# nico.net
KiCad netlist of a schematic drawn in EAGLE
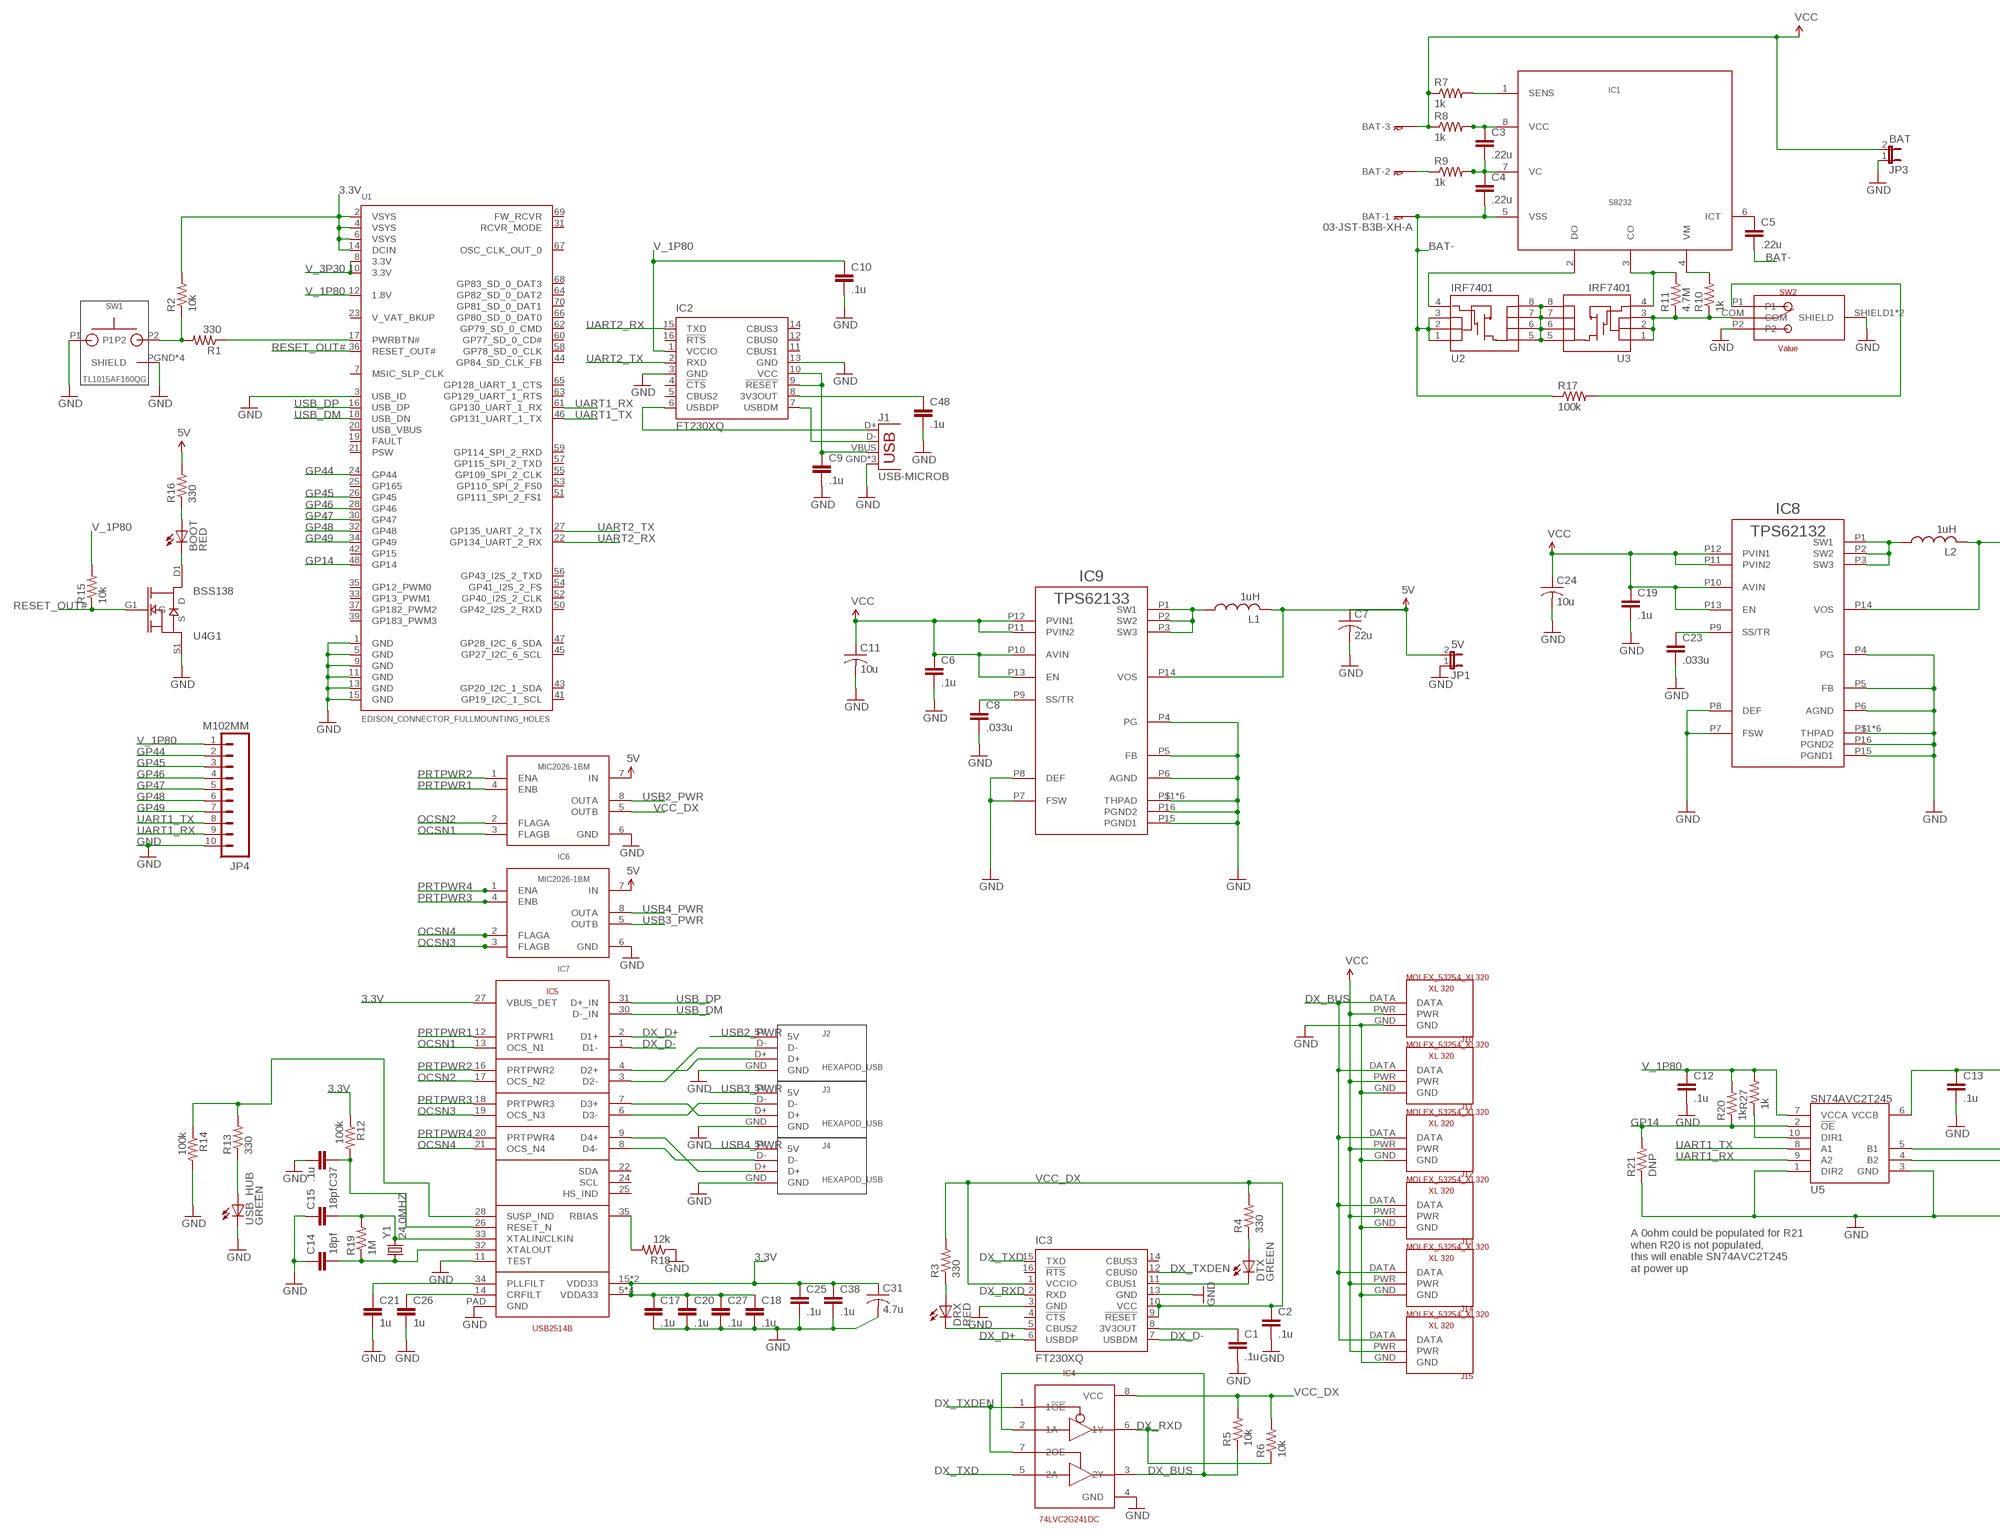
[diagram p0: schematic, sheet 1, part 1 of 2]
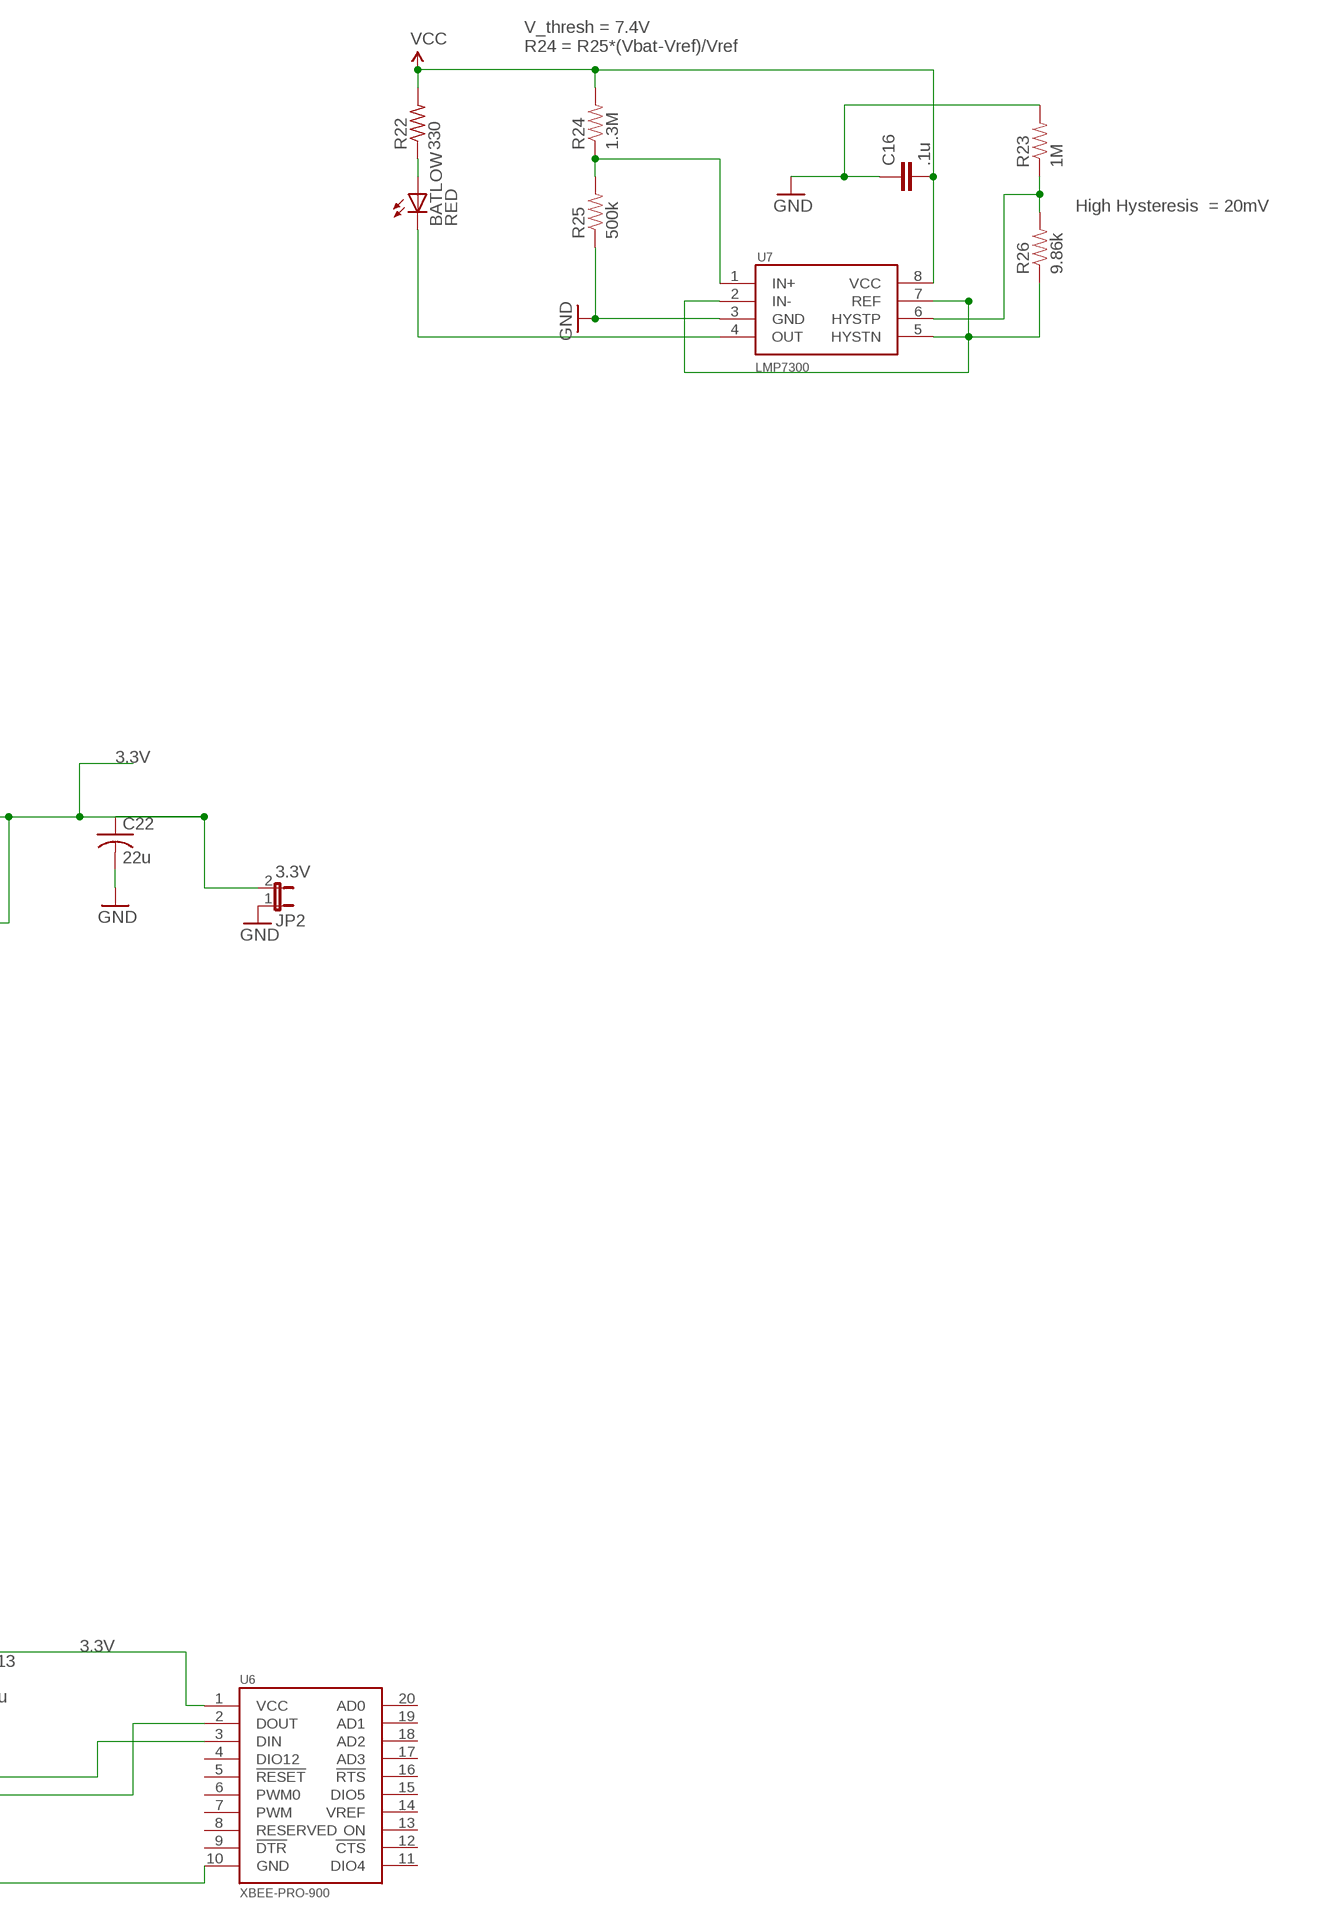
[diagram p1: schematic, sheet 1, part 2 of 2]

(export (version "E")
  (design (tool "Eeschema 10.0.6"))
  (components
    (comp (ref "BAT")
      (value "03-JST-B3B-XH-A")
      (footprint "eagle-import:B3B-XH")
      (libsource (lib "eagle-import") (part "03-JST-B3B-XH-A"))
    )
    (comp (ref "BATLOW")
      (value "RED")
      (footprint "eagle-import:LED-0603")
      (libsource (lib "eagle-import") (part "LED0603"))
    )
    (comp (ref "BOOT")
      (value "RED")
      (footprint "eagle-import:LED-0603")
      (libsource (lib "eagle-import") (part "LED0603"))
    )
    (comp (ref "C1")
      (value ".1u")
      (footprint "eagle-import:C0402")
      (libsource (lib "eagle-import") (part "C-EUC0402"))
    )
    (comp (ref "C2")
      (value ".1u")
      (footprint "eagle-import:C0402")
      (libsource (lib "eagle-import") (part "C-EUC0402"))
    )
    (comp (ref "C3")
      (value ".22u")
      (footprint "eagle-import:C0402")
      (libsource (lib "eagle-import") (part "C-EUC0402"))
    )
    (comp (ref "C4")
      (value ".22u")
      (footprint "eagle-import:C0402")
      (libsource (lib "eagle-import") (part "C-EUC0402"))
    )
    (comp (ref "C5")
      (value ".22u")
      (footprint "eagle-import:C0402")
      (libsource (lib "eagle-import") (part "C-EUC0402"))
    )
    (comp (ref "C6")
      (value ".1u")
      (footprint "eagle-import:C0402")
      (libsource (lib "eagle-import") (part "C-EUC0402"))
    )
    (comp (ref "C7")
      (value "22u")
      (footprint "eagle-import:C0603")
      (libsource (lib "eagle-import") (part "resistor_C-USC0603"))
    )
    (comp (ref "C8")
      (value ".033u")
      (footprint "eagle-import:C0402")
      (libsource (lib "eagle-import") (part "C-EUC0402"))
    )
    (comp (ref "C9")
      (value ".1u")
      (footprint "eagle-import:C0402")
      (libsource (lib "eagle-import") (part "C-EUC0402"))
    )
    (comp (ref "C10")
      (value ".1u")
      (footprint "eagle-import:C0402")
      (libsource (lib "eagle-import") (part "C-EUC0402"))
    )
    (comp (ref "C11")
      (value "10u")
      (footprint "eagle-import:C0805")
      (libsource (lib "eagle-import") (part "C-USC0805"))
    )
    (comp (ref "C12")
      (value ".1u")
      (footprint "eagle-import:C0402")
      (libsource (lib "eagle-import") (part "C-EUC0402"))
    )
    (comp (ref "C13")
      (value ".1u")
      (footprint "eagle-import:C0402")
      (libsource (lib "eagle-import") (part "C-EUC0402"))
    )
    (comp (ref "C14")
      (value "18pf")
      (footprint "eagle-import:C0402")
      (libsource (lib "eagle-import") (part "C-EUC0402"))
    )
    (comp (ref "C15")
      (value "18pf")
      (footprint "eagle-import:C0402")
      (libsource (lib "eagle-import") (part "C-EUC0402"))
    )
    (comp (ref "C16")
      (value ".1u")
      (footprint "eagle-import:C0402")
      (libsource (lib "eagle-import") (part "C-EUC0402"))
    )
    (comp (ref "C17")
      (value ".1u")
      (footprint "eagle-import:C0402")
      (libsource (lib "eagle-import") (part "C-EUC0402"))
    )
    (comp (ref "C18")
      (value ".1u")
      (footprint "eagle-import:C0402")
      (libsource (lib "eagle-import") (part "C-EUC0402"))
    )
    (comp (ref "C19")
      (value ".1u")
      (footprint "eagle-import:C0402")
      (libsource (lib "eagle-import") (part "C-EUC0402"))
    )
    (comp (ref "C20")
      (value ".1u")
      (footprint "eagle-import:C0402")
      (libsource (lib "eagle-import") (part "C-EUC0402"))
    )
    (comp (ref "C21")
      (value "1u")
      (footprint "eagle-import:C0402")
      (libsource (lib "eagle-import") (part "C-EUC0402"))
    )
    (comp (ref "C22")
      (value "22u")
      (footprint "eagle-import:C0603")
      (libsource (lib "eagle-import") (part "resistor_C-USC0603"))
    )
    (comp (ref "C23")
      (value ".033u")
      (footprint "eagle-import:C0402")
      (libsource (lib "eagle-import") (part "C-EUC0402"))
    )
    (comp (ref "C24")
      (value "10u")
      (footprint "eagle-import:C0805")
      (libsource (lib "eagle-import") (part "C-USC0805"))
    )
    (comp (ref "C25")
      (value ".1u")
      (footprint "eagle-import:C0402")
      (libsource (lib "eagle-import") (part "C-EUC0402"))
    )
    (comp (ref "C26")
      (value "1u")
      (footprint "eagle-import:C0402")
      (libsource (lib "eagle-import") (part "C-EUC0402"))
    )
    (comp (ref "C27")
      (value ".1u")
      (footprint "eagle-import:C0402")
      (libsource (lib "eagle-import") (part "C-EUC0402"))
    )
    (comp (ref "C31")
      (value "4.7u")
      (footprint "eagle-import:C0603")
      (libsource (lib "eagle-import") (part "resistor_C-USC0603"))
    )
    (comp (ref "C37")
      (value ".1u")
      (footprint "eagle-import:C0402")
      (libsource (lib "eagle-import") (part "C-EUC0402"))
    )
    (comp (ref "C38")
      (value ".1u")
      (footprint "eagle-import:C0402")
      (libsource (lib "eagle-import") (part "C-EUC0402"))
    )
    (comp (ref "C48")
      (value ".1u")
      (footprint "eagle-import:C0402")
      (libsource (lib "eagle-import") (part "C-EUC0402"))
    )
    (comp (ref "DRX")
      (value "RED")
      (footprint "eagle-import:LED-0603")
      (libsource (lib "eagle-import") (part "LED0603"))
    )
    (comp (ref "DTX")
      (value "GREEN")
      (footprint "eagle-import:LED-0603")
      (libsource (lib "eagle-import") (part "LED0603"))
    )
    (comp (ref "IC1")
      (value "S8232")
      (footprint "eagle-import:TSSOP8")
      (libsource (lib "eagle-import") (part "S8232"))
    )
    (comp (ref "IC2")
      (value "FT230XQ")
      (footprint "eagle-import:QFN16")
      (libsource (lib "eagle-import") (part "FT230XQ"))
    )
    (comp (ref "IC3")
      (value "FT230XQ")
      (footprint "eagle-import:QFN16")
      (libsource (lib "eagle-import") (part "FT230XQ"))
    )
    (comp (ref "IC4")
      (value "74LVC2G241DC")
      (footprint "eagle-import:VSSOP")
      (libsource (lib "eagle-import") (part "74LVC2G241DC"))
    )
    (comp (ref "IC5")
      (value "USB2514B")
      (footprint "eagle-import:36-QFN")
      (libsource (lib "eagle-import") (part "USB2514B"))
    )
    (comp (ref "IC6")
      (value "MIC2026-1BM")
      (footprint "eagle-import:8-SOIC")
      (libsource (lib "eagle-import") (part "MIC2026-1BM"))
    )
    (comp (ref "IC7")
      (value "MIC2026-1BM")
      (footprint "eagle-import:8-SOIC")
      (libsource (lib "eagle-import") (part "MIC2026-1BM"))
    )
    (comp (ref "IC8")
      (value "TPS62132")
      (footprint "eagle-import:VQFN-16")
      (libsource (lib "eagle-import") (part "TPS62133"))
    )
    (comp (ref "IC9")
      (value "TPS62133")
      (footprint "eagle-import:VQFN-16")
      (libsource (lib "eagle-import") (part "TPS62133"))
    )
    (comp (ref "J1")
      (value "USB-MICROB")
      (footprint "eagle-import:USB-MICROB")
      (libsource (lib "eagle-import") (part "USB-MICROB"))
    )
    (comp (ref "J2")
      (value "HEXAPOD_USB")
      (footprint "eagle-import:MOLEX_53254_4POS")
      (libsource (lib "eagle-import") (part "HEXAPOD_USB"))
    )
    (comp (ref "J3")
      (value "HEXAPOD_USB")
      (footprint "eagle-import:MOLEX_53254_4POS")
      (libsource (lib "eagle-import") (part "HEXAPOD_USB"))
    )
    (comp (ref "J4")
      (value "HEXAPOD_USB")
      (footprint "eagle-import:MOLEX_53254_4POS")
      (libsource (lib "eagle-import") (part "HEXAPOD_USB"))
    )
    (comp (ref "J10")
      (value "MOLEX_53254_XL320")
      (footprint "eagle-import:MOLES_53254_XL320")
      (libsource (lib "eagle-import") (part "MOLEX_53254_XL320"))
    )
    (comp (ref "J11")
      (value "MOLEX_53254_XL320")
      (footprint "eagle-import:MOLES_53254_XL320")
      (libsource (lib "eagle-import") (part "MOLEX_53254_XL320"))
    )
    (comp (ref "J12")
      (value "MOLEX_53254_XL320")
      (footprint "eagle-import:MOLES_53254_XL320")
      (libsource (lib "eagle-import") (part "MOLEX_53254_XL320"))
    )
    (comp (ref "J13")
      (value "MOLEX_53254_XL320")
      (footprint "eagle-import:MOLES_53254_XL320")
      (libsource (lib "eagle-import") (part "MOLEX_53254_XL320"))
    )
    (comp (ref "J14")
      (value "MOLEX_53254_XL320")
      (footprint "eagle-import:MOLES_53254_XL320")
      (libsource (lib "eagle-import") (part "MOLEX_53254_XL320"))
    )
    (comp (ref "J15")
      (value "MOLEX_53254_XL320")
      (footprint "eagle-import:MOLES_53254_XL320")
      (libsource (lib "eagle-import") (part "MOLEX_53254_XL320"))
    )
    (comp (ref "JP1")
      (value "5V")
      (footprint "eagle-import:1X02")
      (libsource (lib "eagle-import") (part "JUMPER-2PTH"))
    )
    (comp (ref "JP2")
      (value "3.3V")
      (footprint "eagle-import:1X02")
      (libsource (lib "eagle-import") (part "JUMPER-2PTH"))
    )
    (comp (ref "JP3")
      (value "BAT")
      (footprint "eagle-import:1X02")
      (libsource (lib "eagle-import") (part "JUMPER-2PTH"))
    )
    (comp (ref "JP4")
      (value "M102MM")
      (footprint "eagle-import:1X10-2MM")
      (libsource (lib "eagle-import") (part "M102MM"))
    )
    (comp (ref "L1")
      (value "1uH")
      (footprint "eagle-import:L2825P")
      (libsource (lib "eagle-import") (part "L-USL2825P"))
    )
    (comp (ref "L2")
      (value "1uH")
      (footprint "eagle-import:L2825P")
      (libsource (lib "eagle-import") (part "L-USL2825P"))
    )
    (comp (ref "R1")
      (value "330")
      (footprint "eagle-import:R0402")
      (libsource (lib "eagle-import") (part "R-US_R0402"))
    )
    (comp (ref "R2")
      (value "10k")
      (footprint "eagle-import:R0402")
      (libsource (lib "eagle-import") (part "R-US_R0402"))
    )
    (comp (ref "R3")
      (value "330")
      (footprint "eagle-import:R0402")
      (libsource (lib "eagle-import") (part "R-US_R0402"))
    )
    (comp (ref "R4")
      (value "330")
      (footprint "eagle-import:R0402")
      (libsource (lib "eagle-import") (part "R-US_R0402"))
    )
    (comp (ref "R5")
      (value "10k")
      (footprint "eagle-import:R0402")
      (libsource (lib "eagle-import") (part "R-US_R0402"))
    )
    (comp (ref "R6")
      (value "10k")
      (footprint "eagle-import:R0402")
      (libsource (lib "eagle-import") (part "R-US_R0402"))
    )
    (comp (ref "R7")
      (value "1k")
      (footprint "eagle-import:C0402")
      (libsource (lib "eagle-import") (part "RESISTOR0402"))
    )
    (comp (ref "R8")
      (value "1k")
      (footprint "eagle-import:C0402")
      (libsource (lib "eagle-import") (part "RESISTOR0402"))
    )
    (comp (ref "R9")
      (value "1k")
      (footprint "eagle-import:C0402")
      (libsource (lib "eagle-import") (part "RESISTOR0402"))
    )
    (comp (ref "R10")
      (value "1k")
      (footprint "eagle-import:C0402")
      (libsource (lib "eagle-import") (part "RESISTOR0402"))
    )
    (comp (ref "R11")
      (value "4.7M")
      (footprint "eagle-import:C0402")
      (libsource (lib "eagle-import") (part "RESISTOR0402"))
    )
    (comp (ref "R12")
      (value "100k")
      (footprint "eagle-import:C0402")
      (libsource (lib "eagle-import") (part "RESISTOR0402"))
    )
    (comp (ref "R13")
      (value "330")
      (footprint "eagle-import:R0402")
      (libsource (lib "eagle-import") (part "R-US_R0402"))
    )
    (comp (ref "R14")
      (value "100k")
      (footprint "eagle-import:C0402")
      (libsource (lib "eagle-import") (part "RESISTOR0402"))
    )
    (comp (ref "R15")
      (value "10k")
      (footprint "eagle-import:R0402")
      (libsource (lib "eagle-import") (part "R-US_R0402"))
    )
    (comp (ref "R16")
      (value "330")
      (footprint "eagle-import:R0402")
      (libsource (lib "eagle-import") (part "R-US_R0402"))
    )
    (comp (ref "R17")
      (value "100k")
      (footprint "eagle-import:C0402")
      (libsource (lib "eagle-import") (part "RESISTOR0402"))
    )
    (comp (ref "R18")
      (value "12k")
      (footprint "eagle-import:C0402")
      (libsource (lib "eagle-import") (part "RESISTOR0402"))
    )
    (comp (ref "R19")
      (value "1M")
      (footprint "eagle-import:C0402")
      (libsource (lib "eagle-import") (part "RESISTOR0402"))
    )
    (comp (ref "R20")
      (value "1k")
      (footprint "eagle-import:C0402")
      (libsource (lib "eagle-import") (part "RESISTOR0402"))
    )
    (comp (ref "R21")
      (value "DNP")
      (footprint "eagle-import:C0402")
      (libsource (lib "eagle-import") (part "RESISTOR0402"))
    )
    (comp (ref "R22")
      (value "330")
      (footprint "eagle-import:R0402")
      (libsource (lib "eagle-import") (part "R-US_R0402"))
    )
    (comp (ref "R23")
      (value "1M")
      (footprint "eagle-import:C0402")
      (libsource (lib "eagle-import") (part "RESISTOR0402"))
    )
    (comp (ref "R24")
      (value "1.3M")
      (footprint "eagle-import:C0402")
      (libsource (lib "eagle-import") (part "RESISTOR0402"))
    )
    (comp (ref "R25")
      (value "500k")
      (footprint "eagle-import:C0402")
      (libsource (lib "eagle-import") (part "RESISTOR0402"))
    )
    (comp (ref "R26")
      (value "9.86k")
      (footprint "eagle-import:C0402")
      (libsource (lib "eagle-import") (part "RESISTOR0402"))
    )
    (comp (ref "R27")
      (value "1k")
      (footprint "eagle-import:C0402")
      (libsource (lib "eagle-import") (part "RESISTOR0402"))
    )
    (comp (ref "SW1")
      (value "TL1015AF160QG")
      (footprint "eagle-import:TL1015AF160QG")
      (libsource (lib "eagle-import") (part "TL1015AF160QG"))
    )
    (comp (ref "SW2")
      (value "TOGGLE_SWITCH_ET01MD1AGE")
      (footprint "eagle-import:TOGGLE_SWITCH_ET01MD1AGE")
      (libsource (lib "eagle-import") (part "TOGGLE_SWITCH_ET01MD1AGE"))
    )
    (comp (ref "U1")
      (value "EDISON_CONNECTOR_FULLMOUNTING_HOLES")
      (footprint "eagle-import:EDISON_DAUGHTER")
      (libsource (lib "eagle-import") (part "EDISON_CONNECTOR_FULLMOUNTING_HOLES"))
    )
    (comp (ref "U2")
      (value "IRF7401")
      (footprint "eagle-import:SO08")
      (libsource (lib "eagle-import") (part "MOSFET-NCHANNEL-SOIC8"))
    )
    (comp (ref "U3")
      (value "IRF7401")
      (footprint "eagle-import:SO08")
      (libsource (lib "eagle-import") (part "MOSFET-NCHANNEL-SOIC8"))
    )
    (comp (ref "U4")
      (value "BSS138")
      (footprint "eagle-import:SOT363")
      (libsource (lib "eagle-import") (part "BSS138"))
    )
    (comp (ref "U5")
      (value "SN74AVC2T245")
      (footprint "eagle-import:RSW-UQFN-10")
      (libsource (lib "eagle-import") (part "SN74AVC2T245"))
    )
    (comp (ref "U6")
      (value "XBEE-PRO-900")
      (footprint "eagle-import:XBEE-PRO-OEM")
      (libsource (lib "eagle-import") (part "XBEE-PRO-900"))
    )
    (comp (ref "U7")
      (value "LMP7300")
      (footprint "eagle-import:8-SOIC")
      (libsource (lib "eagle-import") (part "LMP7300"))
    )
    (comp (ref "USB_HUB")
      (value "GREEN")
      (footprint "eagle-import:LED-0603")
      (libsource (lib "eagle-import") (part "LED0603"))
    )
    (comp (ref "Y1")
      (value "24.0MHZ")
      (footprint "eagle-import:CRYSTAL-SMD-5X3")
      (libsource (lib "eagle-import") (part "CRYSTAL5X3"))
    )
  )
  (nets
    (net (code "1") (name "/3.3V") (class "Default")
      (node (ref "C13") (pin "1") (pinfunction "1_1") (pintype "passive"))
      (node (ref "C17") (pin "1") (pinfunction "1_1") (pintype "passive"))
      (node (ref "C18") (pin "1") (pinfunction "1_1") (pintype "passive"))
      (node (ref "C20") (pin "1") (pinfunction "1_1") (pintype "passive"))
      (node (ref "C22") (pin "1") (pinfunction "1_1") (pintype "passive"))
      (node (ref "C25") (pin "1") (pinfunction "1_1") (pintype "passive"))
      (node (ref "C27") (pin "1") (pinfunction "1_1") (pintype "passive"))
      (node (ref "C31") (pin "1") (pinfunction "1_1") (pintype "passive"))
      (node (ref "C38") (pin "1") (pinfunction "1_1") (pintype "passive"))
      (node (ref "IC5") (pin "10") (pinfunction "VDDA33_10") (pintype "bidirectional"))
      (node (ref "IC5") (pin "15") (pinfunction "VDD33_15") (pintype "bidirectional"))
      (node (ref "IC5") (pin "23") (pinfunction "VDD33_23") (pintype "bidirectional"))
      (node (ref "IC5") (pin "27") (pinfunction "VBUS_DET_27") (pintype "bidirectional"))
      (node (ref "IC5") (pin "29") (pinfunction "VDDA33_29") (pintype "bidirectional"))
      (node (ref "IC5") (pin "36") (pinfunction "VDDA33_36") (pintype "bidirectional"))
      (node (ref "IC5") (pin "5") (pinfunction "VDDA33_5") (pintype "bidirectional"))
      (node (ref "IC8") (pin "P14") (pinfunction "VOS_P14") (pintype "bidirectional"))
      (node (ref "JP2") (pin "2") (pinfunction "2_2") (pintype "passive"))
      (node (ref "L2") (pin "2") (pinfunction "2_2") (pintype "passive"))
      (node (ref "R12") (pin "1") (pinfunction "1_1") (pintype "passive"))
      (node (ref "R2") (pin "2") (pinfunction "2_2") (pintype "passive"))
      (node (ref "U1") (pin "14") (pinfunction "DCIN_14") (pintype "bidirectional"))
      (node (ref "U1") (pin "2") (pinfunction "VSYS_2") (pintype "bidirectional"))
      (node (ref "U1") (pin "4") (pinfunction "VSYS_4") (pintype "bidirectional"))
      (node (ref "U1") (pin "6") (pinfunction "VSYS_6") (pintype "bidirectional"))
      (node (ref "U5") (pin "6") (pinfunction "VCCB_6") (pintype "bidirectional"))
      (node (ref "U6") (pin "1") (pinfunction "VCC_1") (pintype "bidirectional"))
    )
    (net (code "2") (name "/BAT-") (class "Default")
      (node (ref "BAT") (pin "P$1") (pinfunction "1_P$1") (pintype "passive"))
      (node (ref "C4") (pin "2") (pinfunction "2_2") (pintype "passive"))
      (node (ref "C5") (pin "2") (pinfunction "2_2") (pintype "passive"))
      (node (ref "IC1") (pin "5") (pinfunction "VSS_5") (pintype "bidirectional"))
      (node (ref "R17") (pin "1") (pinfunction "1_1") (pintype "passive"))
      (node (ref "U2") (pin "1") (pinfunction "S_1") (pintype "bidirectional"))
      (node (ref "U2") (pin "2") (pinfunction "S_2") (pintype "bidirectional"))
      (node (ref "U2") (pin "3") (pinfunction "S_3") (pintype "bidirectional"))
    )
    (net (code "3") (name "/DX_BUS") (class "Default")
      (node (ref "IC4") (pin "2") (pinfunction "1A_2") (pintype "bidirectional"))
      (node (ref "IC4") (pin "3") (pinfunction "2Y_3") (pintype "bidirectional"))
      (node (ref "J10") (pin "DATA") (pinfunction "DATA_DATA") (pintype "bidirectional"))
      (node (ref "J11") (pin "DATA") (pinfunction "DATA_DATA") (pintype "bidirectional"))
      (node (ref "J12") (pin "DATA") (pinfunction "DATA_DATA") (pintype "bidirectional"))
      (node (ref "J13") (pin "DATA") (pinfunction "DATA_DATA") (pintype "bidirectional"))
      (node (ref "J14") (pin "DATA") (pinfunction "DATA_DATA") (pintype "bidirectional"))
      (node (ref "J15") (pin "DATA") (pinfunction "DATA_DATA") (pintype "bidirectional"))
      (node (ref "R5") (pin "1") (pinfunction "1_1") (pintype "passive"))
    )
    (net (code "4") (name "/DX_D+") (class "Default")
      (node (ref "IC3") (pin "6") (pinfunction "USBDP_6") (pintype "input"))
      (node (ref "IC5") (pin "2") (pinfunction "D1+_2") (pintype "bidirectional"))
    )
    (net (code "5") (name "/DX_D-") (class "Default")
      (node (ref "IC3") (pin "7") (pinfunction "USBDM_7") (pintype "input"))
      (node (ref "IC5") (pin "1") (pinfunction "D1-_1") (pintype "bidirectional"))
    )
    (net (code "6") (name "/DX_RXD") (class "Default")
      (node (ref "IC3") (pin "2") (pinfunction "RXD_2") (pintype "input"))
      (node (ref "IC4") (pin "6") (pinfunction "1Y_6") (pintype "bidirectional"))
      (node (ref "R6") (pin "1") (pinfunction "1_1") (pintype "passive"))
    )
    (net (code "7") (name "/DX_TXD") (class "Default")
      (node (ref "IC3") (pin "15") (pinfunction "TXD_15") (pintype "output"))
      (node (ref "IC4") (pin "5") (pinfunction "2A_5") (pintype "bidirectional"))
    )
    (net (code "8") (name "/DX_TXDEN") (class "Default")
      (node (ref "IC3") (pin "12") (pinfunction "CBUS0_12") (pintype "bidirectional"))
      (node (ref "IC4") (pin "1") (pinfunction "1~{OE}_1") (pintype "bidirectional"))
      (node (ref "IC4") (pin "7") (pinfunction "2OE_7") (pintype "bidirectional"))
    )
    (net (code "9") (name "/GP14") (class "Default")
      (node (ref "R20") (pin "1") (pinfunction "1_1") (pintype "passive"))
      (node (ref "R21") (pin "2") (pinfunction "2_2") (pintype "passive"))
      (node (ref "U1") (pin "48") (pinfunction "GP14_48") (pintype "bidirectional"))
      (node (ref "U5") (pin "2") (pinfunction "~{OE}_2") (pintype "bidirectional"))
    )
    (net (code "10") (name "/GP44") (class "Default")
      (node (ref "JP4") (pin "2") (pinfunction "2_2") (pintype "passive"))
      (node (ref "U1") (pin "24") (pinfunction "GP44_24") (pintype "bidirectional"))
    )
    (net (code "11") (name "/GP45") (class "Default")
      (node (ref "JP4") (pin "3") (pinfunction "3_3") (pintype "passive"))
      (node (ref "U1") (pin "26") (pinfunction "GP45_26") (pintype "bidirectional"))
    )
    (net (code "12") (name "/GP46") (class "Default")
      (node (ref "JP4") (pin "4") (pinfunction "4_4") (pintype "passive"))
      (node (ref "U1") (pin "28") (pinfunction "GP46_28") (pintype "bidirectional"))
    )
    (net (code "13") (name "/GP47") (class "Default")
      (node (ref "JP4") (pin "5") (pinfunction "5_5") (pintype "passive"))
      (node (ref "U1") (pin "30") (pinfunction "GP47_30") (pintype "bidirectional"))
    )
    (net (code "14") (name "/GP48") (class "Default")
      (node (ref "JP4") (pin "6") (pinfunction "6_6") (pintype "passive"))
      (node (ref "U1") (pin "32") (pinfunction "GP48_32") (pintype "bidirectional"))
    )
    (net (code "15") (name "/GP49") (class "Default")
      (node (ref "JP4") (pin "7") (pinfunction "7_7") (pintype "passive"))
      (node (ref "U1") (pin "34") (pinfunction "GP49_34") (pintype "bidirectional"))
    )
    (net (code "16") (name "/OCSN1") (class "Default")
      (node (ref "IC5") (pin "13") (pinfunction "OCS_N1_13") (pintype "bidirectional"))
      (node (ref "IC6") (pin "3") (pinfunction "FLAGB_3") (pintype "bidirectional"))
    )
    (net (code "17") (name "/OCSN2") (class "Default")
      (node (ref "IC5") (pin "17") (pinfunction "OCS_N2_17") (pintype "bidirectional"))
      (node (ref "IC6") (pin "2") (pinfunction "FLAGA_2") (pintype "bidirectional"))
    )
    (net (code "18") (name "/OCSN3") (class "Default")
      (node (ref "IC5") (pin "19") (pinfunction "OCS_N3_19") (pintype "bidirectional"))
      (node (ref "IC7") (pin "3") (pinfunction "FLAGB_3") (pintype "bidirectional"))
    )
    (net (code "19") (name "/OCSN4") (class "Default")
      (node (ref "IC5") (pin "21") (pinfunction "OCS_N4_21") (pintype "bidirectional"))
      (node (ref "IC7") (pin "2") (pinfunction "FLAGA_2") (pintype "bidirectional"))
    )
    (net (code "20") (name "/PRTPWR1") (class "Default")
      (node (ref "IC5") (pin "12") (pinfunction "PRTPWR1_12") (pintype "bidirectional"))
      (node (ref "IC6") (pin "4") (pinfunction "ENB_4") (pintype "bidirectional"))
    )
    (net (code "21") (name "/PRTPWR2") (class "Default")
      (node (ref "IC5") (pin "16") (pinfunction "PRTPWR2_16") (pintype "bidirectional"))
      (node (ref "IC6") (pin "1") (pinfunction "ENA_1") (pintype "bidirectional"))
    )
    (net (code "22") (name "/PRTPWR3") (class "Default")
      (node (ref "IC5") (pin "18") (pinfunction "PRTPWR3_18") (pintype "bidirectional"))
      (node (ref "IC7") (pin "4") (pinfunction "ENB_4") (pintype "bidirectional"))
    )
    (net (code "23") (name "/PRTPWR4") (class "Default")
      (node (ref "IC5") (pin "20") (pinfunction "PRTPWR4_20") (pintype "bidirectional"))
      (node (ref "IC7") (pin "1") (pinfunction "ENA_1") (pintype "bidirectional"))
    )
    (net (code "24") (name "/RESET_OUT#") (class "Default")
      (node (ref "R15") (pin "1") (pinfunction "1_1") (pintype "passive"))
      (node (ref "U1") (pin "36") (pinfunction "RESET_OUT#_36") (pintype "bidirectional"))
      (node (ref "U4") (pin "G1") (pinfunction "G_G1") (pintype "bidirectional"))
    )
    (net (code "25") (name "/UART1_RX") (class "Default")
      (node (ref "JP4") (pin "9") (pinfunction "9_9") (pintype "passive"))
      (node (ref "U1") (pin "61") (pinfunction "GP130_UART_1_RX_61") (pintype "bidirectional"))
      (node (ref "U5") (pin "9") (pinfunction "A2_9") (pintype "bidirectional"))
    )
    (net (code "26") (name "/UART1_TX") (class "Default")
      (node (ref "JP4") (pin "8") (pinfunction "8_8") (pintype "passive"))
      (node (ref "U1") (pin "46") (pinfunction "GP131_UART_1_TX_46") (pintype "bidirectional"))
      (node (ref "U5") (pin "8") (pinfunction "A1_8") (pintype "bidirectional"))
    )
    (net (code "27") (name "/UART2_RX") (class "Default")
      (node (ref "IC2") (pin "15") (pinfunction "TXD_15") (pintype "output"))
      (node (ref "U1") (pin "22") (pinfunction "GP134_UART_2_RX_22") (pintype "bidirectional"))
    )
    (net (code "28") (name "/UART2_TX") (class "Default")
      (node (ref "IC2") (pin "2") (pinfunction "RXD_2") (pintype "input"))
      (node (ref "U1") (pin "27") (pinfunction "GP135_UART_2_TX_27") (pintype "bidirectional"))
    )
    (net (code "29") (name "/USB2_PWR") (class "Default")
      (node (ref "IC6") (pin "8") (pinfunction "OUTA_8") (pintype "bidirectional"))
      (node (ref "J2") (pin "5V") (pinfunction "5V_5V") (pintype "bidirectional"))
    )
    (net (code "30") (name "/USB3_PWR") (class "Default")
      (node (ref "IC7") (pin "5") (pinfunction "OUTB_5") (pintype "bidirectional"))
      (node (ref "J3") (pin "5V") (pinfunction "5V_5V") (pintype "bidirectional"))
    )
    (net (code "31") (name "/USB4_PWR") (class "Default")
      (node (ref "IC7") (pin "8") (pinfunction "OUTA_8") (pintype "bidirectional"))
      (node (ref "J4") (pin "5V") (pinfunction "5V_5V") (pintype "bidirectional"))
    )
    (net (code "32") (name "/USB_DM") (class "Default")
      (node (ref "IC5") (pin "30") (pinfunction "D-_IN_30") (pintype "bidirectional"))
      (node (ref "U1") (pin "18") (pinfunction "USB_DN_18") (pintype "bidirectional"))
    )
    (net (code "33") (name "/USB_DP") (class "Default")
      (node (ref "IC5") (pin "31") (pinfunction "D+_IN_31") (pintype "bidirectional"))
      (node (ref "U1") (pin "16") (pinfunction "USB_DP_16") (pintype "bidirectional"))
    )
    (net (code "34") (name "/VCC_DX") (class "Default")
      (node (ref "C2") (pin "1") (pinfunction "1_1") (pintype "passive"))
      (node (ref "IC3") (pin "1") (pinfunction "VCCIO_1") (pintype "power_in"))
      (node (ref "IC3") (pin "10") (pinfunction "VCC_10") (pintype "power_in"))
      (node (ref "IC3") (pin "9") (pinfunction "~{RESET}_9") (pintype "input"))
      (node (ref "IC4") (pin "8") (pinfunction "VCC_8") (pintype "bidirectional"))
      (node (ref "IC6") (pin "5") (pinfunction "OUTB_5") (pintype "bidirectional"))
      (node (ref "R3") (pin "2") (pinfunction "2_2") (pintype "passive"))
      (node (ref "R4") (pin "2") (pinfunction "2_2") (pintype "passive"))
      (node (ref "R5") (pin "2") (pinfunction "2_2") (pintype "passive"))
      (node (ref "R6") (pin "2") (pinfunction "2_2") (pintype "passive"))
    )
    (net (code "35") (name "/V_1P80") (class "Default")
      (node (ref "C10") (pin "1") (pinfunction "1_1") (pintype "passive"))
      (node (ref "C12") (pin "1") (pinfunction "1_1") (pintype "passive"))
      (node (ref "IC2") (pin "1") (pinfunction "VCCIO_1") (pintype "power_in"))
      (node (ref "JP4") (pin "1") (pinfunction "1_1") (pintype "passive"))
      (node (ref "R15") (pin "2") (pinfunction "2_2") (pintype "passive"))
      (node (ref "R20") (pin "2") (pinfunction "2_2") (pintype "passive"))
      (node (ref "R27") (pin "2") (pinfunction "2_2") (pintype "passive"))
      (node (ref "U1") (pin "12") (pinfunction "1.8V_12") (pintype "bidirectional"))
      (node (ref "U5") (pin "7") (pinfunction "VCCA_7") (pintype "bidirectional"))
    )
    (net (code "36") (name "/V_3P30") (class "Default")
      (node (ref "U1") (pin "10") (pinfunction "3.3V_10") (pintype "bidirectional"))
      (node (ref "U1") (pin "8") (pinfunction "3.3V_8") (pintype "bidirectional"))
    )
    (net (code "37") (name "5V") (class "Default")
      (node (ref "C7") (pin "1") (pinfunction "1_1") (pintype "passive"))
      (node (ref "IC6") (pin "7") (pinfunction "IN_7") (pintype "bidirectional"))
      (node (ref "IC7") (pin "7") (pinfunction "IN_7") (pintype "bidirectional"))
      (node (ref "IC9") (pin "P14") (pinfunction "VOS_P14") (pintype "bidirectional"))
      (node (ref "JP1") (pin "2") (pinfunction "2_2") (pintype "passive"))
      (node (ref "L1") (pin "2") (pinfunction "2_2") (pintype "passive"))
      (node (ref "R16") (pin "2") (pinfunction "2_2") (pintype "passive"))
    )
    (net (code "38") (name "GND") (class "Default")
      (node (ref "C1") (pin "2") (pinfunction "2_2") (pintype "passive"))
      (node (ref "C10") (pin "2") (pinfunction "2_2") (pintype "passive"))
      (node (ref "C11") (pin "2") (pinfunction "2_2") (pintype "passive"))
      (node (ref "C12") (pin "2") (pinfunction "2_2") (pintype "passive"))
      (node (ref "C13") (pin "2") (pinfunction "2_2") (pintype "passive"))
      (node (ref "C14") (pin "1") (pinfunction "1_1") (pintype "passive"))
      (node (ref "C15") (pin "1") (pinfunction "1_1") (pintype "passive"))
      (node (ref "C16") (pin "1") (pinfunction "1_1") (pintype "passive"))
      (node (ref "C17") (pin "2") (pinfunction "2_2") (pintype "passive"))
      (node (ref "C18") (pin "2") (pinfunction "2_2") (pintype "passive"))
      (node (ref "C19") (pin "2") (pinfunction "2_2") (pintype "passive"))
      (node (ref "C2") (pin "2") (pinfunction "2_2") (pintype "passive"))
      (node (ref "C20") (pin "2") (pinfunction "2_2") (pintype "passive"))
      (node (ref "C21") (pin "2") (pinfunction "2_2") (pintype "passive"))
      (node (ref "C22") (pin "2") (pinfunction "2_2") (pintype "passive"))
      (node (ref "C23") (pin "2") (pinfunction "2_2") (pintype "passive"))
      (node (ref "C24") (pin "2") (pinfunction "2_2") (pintype "passive"))
      (node (ref "C25") (pin "2") (pinfunction "2_2") (pintype "passive"))
      (node (ref "C26") (pin "2") (pinfunction "2_2") (pintype "passive"))
      (node (ref "C27") (pin "2") (pinfunction "2_2") (pintype "passive"))
      (node (ref "C31") (pin "2") (pinfunction "2_2") (pintype "passive"))
      (node (ref "C37") (pin "2") (pinfunction "2_2") (pintype "passive"))
      (node (ref "C38") (pin "2") (pinfunction "2_2") (pintype "passive"))
      (node (ref "C48") (pin "2") (pinfunction "2_2") (pintype "passive"))
      (node (ref "C6") (pin "2") (pinfunction "2_2") (pintype "passive"))
      (node (ref "C7") (pin "2") (pinfunction "2_2") (pintype "passive"))
      (node (ref "C8") (pin "2") (pinfunction "2_2") (pintype "passive"))
      (node (ref "C9") (pin "2") (pinfunction "2_2") (pintype "passive"))
      (node (ref "IC2") (pin "13") (pinfunction "GND_13") (pintype "power_in"))
      (node (ref "IC2") (pin "3") (pinfunction "GND_3") (pintype "power_in"))
      (node (ref "IC3") (pin "13") (pinfunction "GND_13") (pintype "power_in"))
      (node (ref "IC3") (pin "3") (pinfunction "GND_3") (pintype "power_in"))
      (node (ref "IC4") (pin "4") (pinfunction "GND_4") (pintype "bidirectional"))
      (node (ref "IC5") (pin "11") (pinfunction "TEST_11") (pintype "bidirectional"))
      (node (ref "IC5") (pin "PAD") (pinfunction "GND_PAD") (pintype "bidirectional"))
      (node (ref "IC6") (pin "6") (pinfunction "GND_6") (pintype "bidirectional"))
      (node (ref "IC7") (pin "6") (pinfunction "GND_6") (pintype "bidirectional"))
      (node (ref "IC8") (pin "P$1") (pinfunction "THPAD_P$1") (pintype "bidirectional"))
      (node (ref "IC8") (pin "P$2") (pinfunction "THPAD_P$2") (pintype "bidirectional"))
      (node (ref "IC8") (pin "P$3") (pinfunction "THPAD_P$3") (pintype "bidirectional"))
      (node (ref "IC8") (pin "P$4") (pinfunction "THPAD_P$4") (pintype "bidirectional"))
      (node (ref "IC8") (pin "P$5") (pinfunction "THPAD_P$5") (pintype "bidirectional"))
      (node (ref "IC8") (pin "P$6") (pinfunction "THPAD_P$6") (pintype "bidirectional"))
      (node (ref "IC8") (pin "P15") (pinfunction "PGND1_P15") (pintype "bidirectional"))
      (node (ref "IC8") (pin "P16") (pinfunction "PGND2_P16") (pintype "bidirectional"))
      (node (ref "IC8") (pin "P4") (pinfunction "PG_P4") (pintype "bidirectional"))
      (node (ref "IC8") (pin "P5") (pinfunction "FB_P5") (pintype "bidirectional"))
      (node (ref "IC8") (pin "P6") (pinfunction "AGND_P6") (pintype "bidirectional"))
      (node (ref "IC8") (pin "P7") (pinfunction "FSW_P7") (pintype "bidirectional"))
      (node (ref "IC8") (pin "P8") (pinfunction "DEF_P8") (pintype "bidirectional"))
      (node (ref "IC9") (pin "P$1") (pinfunction "THPAD_P$1") (pintype "bidirectional"))
      (node (ref "IC9") (pin "P$2") (pinfunction "THPAD_P$2") (pintype "bidirectional"))
      (node (ref "IC9") (pin "P$3") (pinfunction "THPAD_P$3") (pintype "bidirectional"))
      (node (ref "IC9") (pin "P$4") (pinfunction "THPAD_P$4") (pintype "bidirectional"))
      (node (ref "IC9") (pin "P$5") (pinfunction "THPAD_P$5") (pintype "bidirectional"))
      (node (ref "IC9") (pin "P$6") (pinfunction "THPAD_P$6") (pintype "bidirectional"))
      (node (ref "IC9") (pin "P15") (pinfunction "PGND1_P15") (pintype "bidirectional"))
      (node (ref "IC9") (pin "P16") (pinfunction "PGND2_P16") (pintype "bidirectional"))
      (node (ref "IC9") (pin "P4") (pinfunction "PG_P4") (pintype "bidirectional"))
      (node (ref "IC9") (pin "P5") (pinfunction "FB_P5") (pintype "bidirectional"))
      (node (ref "IC9") (pin "P6") (pinfunction "AGND_P6") (pintype "bidirectional"))
      (node (ref "IC9") (pin "P7") (pinfunction "FSW_P7") (pintype "bidirectional"))
      (node (ref "IC9") (pin "P8") (pinfunction "DEF_P8") (pintype "bidirectional"))
      (node (ref "J1") (pin "GND") (pinfunction "GND_GND") (pintype "bidirectional"))
      (node (ref "J1") (pin "MT1") (pinfunction "GND_MT1") (pintype "bidirectional"))
      (node (ref "J1") (pin "MT2") (pinfunction "GND_MT2") (pintype "bidirectional"))
      (node (ref "J10") (pin "GND") (pinfunction "GND_GND") (pintype "bidirectional"))
      (node (ref "J11") (pin "GND") (pinfunction "GND_GND") (pintype "bidirectional"))
      (node (ref "J12") (pin "GND") (pinfunction "GND_GND") (pintype "bidirectional"))
      (node (ref "J13") (pin "GND") (pinfunction "GND_GND") (pintype "bidirectional"))
      (node (ref "J14") (pin "GND") (pinfunction "GND_GND") (pintype "bidirectional"))
      (node (ref "J15") (pin "GND") (pinfunction "GND_GND") (pintype "bidirectional"))
      (node (ref "J2") (pin "GND") (pinfunction "GND_GND") (pintype "bidirectional"))
      (node (ref "J3") (pin "GND") (pinfunction "GND_GND") (pintype "bidirectional"))
      (node (ref "J4") (pin "GND") (pinfunction "GND_GND") (pintype "bidirectional"))
      (node (ref "JP1") (pin "1") (pinfunction "1_1") (pintype "passive"))
      (node (ref "JP2") (pin "1") (pinfunction "1_1") (pintype "passive"))
      (node (ref "JP3") (pin "1") (pinfunction "1_1") (pintype "passive"))
      (node (ref "JP4") (pin "10") (pinfunction "10_10") (pintype "passive"))
      (node (ref "R14") (pin "2") (pinfunction "2_2") (pintype "passive"))
      (node (ref "R18") (pin "1") (pinfunction "1_1") (pintype "passive"))
      (node (ref "R21") (pin "1") (pinfunction "1_1") (pintype "passive"))
      (node (ref "R23") (pin "2") (pinfunction "2_2") (pintype "passive"))
      (node (ref "R25") (pin "1") (pinfunction "1_1") (pintype "passive"))
      (node (ref "SW1") (pin "P1") (pinfunction "P1_P1") (pintype "bidirectional"))
      (node (ref "SW1") (pin "PGND") (pinfunction "SHIELD_PGND") (pintype "bidirectional"))
      (node (ref "SW1") (pin "PGND2") (pinfunction "SHIELD_PGND2") (pintype "bidirectional"))
      (node (ref "SW1") (pin "PGND3") (pinfunction "SHIELD_PGND3") (pintype "bidirectional"))
      (node (ref "SW1") (pin "PGND4") (pinfunction "SHIELD_PGND4") (pintype "bidirectional"))
      (node (ref "SW2") (pin "P2") (pinfunction "P2_P2") (pintype "bidirectional"))
      (node (ref "SW2") (pin "SHIELD1") (pinfunction "SHIELD_SHIELD1") (pintype "bidirectional"))
      (node (ref "SW2") (pin "SHIELD2") (pinfunction "SHIELD_SHIELD2") (pintype "bidirectional"))
      (node (ref "U1") (pin "1") (pinfunction "GND_1") (pintype "bidirectional"))
      (node (ref "U1") (pin "11") (pinfunction "GND_11") (pintype "bidirectional"))
      (node (ref "U1") (pin "13") (pinfunction "GND_13") (pintype "bidirectional"))
      (node (ref "U1") (pin "15") (pinfunction "GND_15") (pintype "bidirectional"))
      (node (ref "U1") (pin "3") (pinfunction "USB_ID_3") (pintype "bidirectional"))
      (node (ref "U1") (pin "5") (pinfunction "GND_5") (pintype "bidirectional"))
      (node (ref "U1") (pin "9") (pinfunction "GND_9") (pintype "bidirectional"))
      (node (ref "U4") (pin "S1") (pinfunction "S_S1") (pintype "bidirectional"))
      (node (ref "U5") (pin "1") (pinfunction "DIR2_1") (pintype "bidirectional"))
      (node (ref "U5") (pin "3") (pinfunction "GND_3") (pintype "bidirectional"))
      (node (ref "U6") (pin "10") (pinfunction "GND_10") (pintype "bidirectional"))
      (node (ref "U7") (pin "3") (pinfunction "GND_3") (pintype "bidirectional"))
      (node (ref "USB_HUB") (pin "C") (pinfunction "C_C") (pintype "passive"))
    )
    (net (code "39") (name "Net-(BATB-1)") (class "Default")
      (node (ref "BAT") (pin "P$2") (pinfunction "1_P$2") (pintype "passive"))
      (node (ref "R9") (pin "1") (pinfunction "1_1") (pintype "passive"))
    )
    (net (code "40") (name "Net-(BATLOW-PadA)") (class "Default")
      (node (ref "BATLOW") (pin "A") (pinfunction "A_A") (pintype "passive"))
      (node (ref "R22") (pin "1") (pinfunction "1_1") (pintype "passive"))
    )
    (net (code "41") (name "Net-(BOOT-PadA)") (class "Default")
      (node (ref "BOOT") (pin "A") (pinfunction "A_A") (pintype "passive"))
      (node (ref "R16") (pin "1") (pinfunction "1_1") (pintype "passive"))
    )
    (net (code "42") (name "Net-(DRX-PadA)") (class "Default")
      (node (ref "DRX") (pin "A") (pinfunction "A_A") (pintype "passive"))
      (node (ref "R3") (pin "1") (pinfunction "1_1") (pintype "passive"))
    )
    (net (code "43") (name "Net-(DTX-PadA)") (class "Default")
      (node (ref "DTX") (pin "A") (pinfunction "A_A") (pintype "passive"))
      (node (ref "R4") (pin "1") (pinfunction "1_1") (pintype "passive"))
    )
    (net (code "44") (name "Net-(IC1-CO)") (class "Default")
      (node (ref "IC1") (pin "3") (pinfunction "CO_3") (pintype "bidirectional"))
      (node (ref "R11") (pin "2") (pinfunction "2_2") (pintype "passive"))
      (node (ref "U3") (pin "4") (pinfunction "G_4") (pintype "bidirectional"))
    )
    (net (code "45") (name "Net-(IC1-DO)") (class "Default")
      (node (ref "IC1") (pin "2") (pinfunction "DO_2") (pintype "bidirectional"))
      (node (ref "U2") (pin "4") (pinfunction "G_4") (pintype "bidirectional"))
    )
    (net (code "46") (name "Net-(IC1-ICT)") (class "Default")
      (node (ref "C5") (pin "1") (pinfunction "1_1") (pintype "passive"))
      (node (ref "IC1") (pin "6") (pinfunction "ICT_6") (pintype "bidirectional"))
    )
    (net (code "47") (name "Net-(IC1-SENS)") (class "Default")
      (node (ref "IC1") (pin "1") (pinfunction "SENS_1") (pintype "bidirectional"))
      (node (ref "R7") (pin "2") (pinfunction "2_2") (pintype "passive"))
    )
    (net (code "48") (name "Net-(IC1-VC)") (class "Default")
      (node (ref "C3") (pin "2") (pinfunction "2_2") (pintype "passive"))
      (node (ref "C4") (pin "1") (pinfunction "1_1") (pintype "passive"))
      (node (ref "IC1") (pin "7") (pinfunction "VC_7") (pintype "bidirectional"))
      (node (ref "R9") (pin "2") (pinfunction "2_2") (pintype "passive"))
    )
    (net (code "49") (name "Net-(IC1-VCC)") (class "Default")
      (node (ref "C3") (pin "1") (pinfunction "1_1") (pintype "passive"))
      (node (ref "IC1") (pin "8") (pinfunction "VCC_8") (pintype "bidirectional"))
      (node (ref "R8") (pin "2") (pinfunction "2_2") (pintype "passive"))
    )
    (net (code "50") (name "Net-(IC1-VM)") (class "Default")
      (node (ref "IC1") (pin "4") (pinfunction "VM_4") (pintype "bidirectional"))
      (node (ref "R10") (pin "2") (pinfunction "2_2") (pintype "passive"))
    )
    (net (code "51") (name "Net-(IC2-3V3OUT)") (class "Default")
      (node (ref "C48") (pin "1") (pinfunction "1_1") (pintype "passive"))
      (node (ref "IC2") (pin "8") (pinfunction "3V3OUT_8") (pintype "output"))
    )
    (net (code "52") (name "Net-(IC2-USBDM)") (class "Default")
      (node (ref "IC2") (pin "7") (pinfunction "USBDM_7") (pintype "input"))
      (node (ref "J1") (pin "D-") (pinfunction "D-_D-") (pintype "bidirectional"))
    )
    (net (code "53") (name "Net-(IC2-USBDP)") (class "Default")
      (node (ref "IC2") (pin "6") (pinfunction "USBDP_6") (pintype "input"))
      (node (ref "J1") (pin "D+") (pinfunction "D+_D+") (pintype "bidirectional"))
    )
    (net (code "54") (name "Net-(IC2-VCC)") (class "Default")
      (node (ref "C9") (pin "1") (pinfunction "1_1") (pintype "passive"))
      (node (ref "IC2") (pin "10") (pinfunction "VCC_10") (pintype "power_in"))
      (node (ref "IC2") (pin "9") (pinfunction "~{RESET}_9") (pintype "input"))
      (node (ref "J1") (pin "VBUS") (pinfunction "VBUS_VBUS") (pintype "bidirectional"))
    )
    (net (code "55") (name "Net-(IC3-3V3OUT)") (class "Default")
      (node (ref "C1") (pin "1") (pinfunction "1_1") (pintype "passive"))
      (node (ref "IC3") (pin "8") (pinfunction "3V3OUT_8") (pintype "output"))
    )
    (net (code "56") (name "Net-(IC3-CBUS1)") (class "Default")
      (node (ref "DTX") (pin "C") (pinfunction "C_C") (pintype "passive"))
      (node (ref "IC3") (pin "11") (pinfunction "CBUS1_11") (pintype "bidirectional"))
    )
    (net (code "57") (name "Net-(IC3-CBUS2)") (class "Default")
      (node (ref "DRX") (pin "C") (pinfunction "C_C") (pintype "passive"))
      (node (ref "IC3") (pin "5") (pinfunction "CBUS2_5") (pintype "bidirectional"))
    )
    (net (code "58") (name "Net-(IC5-CRFILT)") (class "Default")
      (node (ref "C26") (pin "1") (pinfunction "1_1") (pintype "passive"))
      (node (ref "IC5") (pin "14") (pinfunction "CRFILT_14") (pintype "bidirectional"))
    )
    (net (code "59") (name "Net-(IC5-D2+)") (class "Default")
      (node (ref "IC5") (pin "4") (pinfunction "D2+_4") (pintype "bidirectional"))
      (node (ref "J2") (pin "D+") (pinfunction "D+_D+") (pintype "bidirectional"))
    )
    (net (code "60") (name "Net-(IC5-D2-)") (class "Default")
      (node (ref "IC5") (pin "3") (pinfunction "D2-_3") (pintype "bidirectional"))
      (node (ref "J2") (pin "D-") (pinfunction "D-_D-") (pintype "bidirectional"))
    )
    (net (code "61") (name "Net-(IC5-D3+)") (class "Default")
      (node (ref "IC5") (pin "7") (pinfunction "D3+_7") (pintype "bidirectional"))
      (node (ref "J3") (pin "D+") (pinfunction "D+_D+") (pintype "bidirectional"))
    )
    (net (code "62") (name "Net-(IC5-D3-)") (class "Default")
      (node (ref "IC5") (pin "6") (pinfunction "D3-_6") (pintype "bidirectional"))
      (node (ref "J3") (pin "D-") (pinfunction "D-_D-") (pintype "bidirectional"))
    )
    (net (code "63") (name "Net-(IC5-D4+)") (class "Default")
      (node (ref "IC5") (pin "9") (pinfunction "D4+_9") (pintype "bidirectional"))
      (node (ref "J4") (pin "D+") (pinfunction "D+_D+") (pintype "bidirectional"))
    )
    (net (code "64") (name "Net-(IC5-D4-)") (class "Default")
      (node (ref "IC5") (pin "8") (pinfunction "D4-_8") (pintype "bidirectional"))
      (node (ref "J4") (pin "D-") (pinfunction "D-_D-") (pintype "bidirectional"))
    )
    (net (code "65") (name "Net-(IC5-PLLFILT)") (class "Default")
      (node (ref "C21") (pin "1") (pinfunction "1_1") (pintype "passive"))
      (node (ref "IC5") (pin "34") (pinfunction "PLLFILT_34") (pintype "bidirectional"))
    )
    (net (code "66") (name "Net-(IC5-RBIAS)") (class "Default")
      (node (ref "IC5") (pin "35") (pinfunction "RBIAS_35") (pintype "bidirectional"))
      (node (ref "R18") (pin "2") (pinfunction "2_2") (pintype "passive"))
    )
    (net (code "67") (name "Net-(IC5-RESET_N)") (class "Default")
      (node (ref "C37") (pin "1") (pinfunction "1_1") (pintype "passive"))
      (node (ref "IC5") (pin "26") (pinfunction "RESET_N_26") (pintype "bidirectional"))
      (node (ref "R12") (pin "2") (pinfunction "2_2") (pintype "passive"))
    )
    (net (code "68") (name "Net-(IC5-SUSP_IND)") (class "Default")
      (node (ref "IC5") (pin "28") (pinfunction "SUSP_IND_28") (pintype "bidirectional"))
      (node (ref "R13") (pin "2") (pinfunction "2_2") (pintype "passive"))
      (node (ref "R14") (pin "1") (pinfunction "1_1") (pintype "passive"))
    )
    (net (code "69") (name "Net-(IC5-XTALIN{slash}CLKIN)") (class "Default")
      (node (ref "C15") (pin "2") (pinfunction "2_2") (pintype "passive"))
      (node (ref "IC5") (pin "33") (pinfunction "XTALIN/CLKIN_33") (pintype "bidirectional"))
      (node (ref "R19") (pin "2") (pinfunction "2_2") (pintype "passive"))
      (node (ref "Y1") (pin "3") (pinfunction "2_3") (pintype "passive"))
    )
    (net (code "70") (name "Net-(IC5-XTALOUT)") (class "Default")
      (node (ref "C14") (pin "2") (pinfunction "2_2") (pintype "passive"))
      (node (ref "IC5") (pin "32") (pinfunction "XTALOUT_32") (pintype "bidirectional"))
      (node (ref "R19") (pin "1") (pinfunction "1_1") (pintype "passive"))
      (node (ref "Y1") (pin "1") (pinfunction "1_1") (pintype "passive"))
    )
    (net (code "71") (name "Net-(IC8-SS{slash}TR)") (class "Default")
      (node (ref "C23") (pin "1") (pinfunction "1_1") (pintype "passive"))
      (node (ref "IC8") (pin "P9") (pinfunction "SS/TR_P9") (pintype "bidirectional"))
    )
    (net (code "72") (name "Net-(IC8-SW1)") (class "Default")
      (node (ref "IC8") (pin "P1") (pinfunction "SW1_P1") (pintype "bidirectional"))
      (node (ref "IC8") (pin "P2") (pinfunction "SW2_P2") (pintype "bidirectional"))
      (node (ref "IC8") (pin "P3") (pinfunction "SW3_P3") (pintype "bidirectional"))
      (node (ref "L2") (pin "1") (pinfunction "1_1") (pintype "passive"))
    )
    (net (code "73") (name "Net-(IC9-SS{slash}TR)") (class "Default")
      (node (ref "C8") (pin "1") (pinfunction "1_1") (pintype "passive"))
      (node (ref "IC9") (pin "P9") (pinfunction "SS/TR_P9") (pintype "bidirectional"))
    )
    (net (code "74") (name "Net-(IC9-SW1)") (class "Default")
      (node (ref "IC9") (pin "P1") (pinfunction "SW1_P1") (pintype "bidirectional"))
      (node (ref "IC9") (pin "P2") (pinfunction "SW2_P2") (pintype "bidirectional"))
      (node (ref "IC9") (pin "P3") (pinfunction "SW3_P3") (pintype "bidirectional"))
      (node (ref "L1") (pin "1") (pinfunction "1_1") (pintype "passive"))
    )
    (net (code "75") (name "Net-(R1-Pad2)") (class "Default")
      (node (ref "R1") (pin "2") (pinfunction "2_2") (pintype "passive"))
      (node (ref "R2") (pin "1") (pinfunction "1_1") (pintype "passive"))
      (node (ref "SW1") (pin "P2") (pinfunction "P2_P2") (pintype "bidirectional"))
    )
    (net (code "76") (name "Net-(R10-Pad1)") (class "Default")
      (node (ref "R10") (pin "1") (pinfunction "1_1") (pintype "passive"))
      (node (ref "R11") (pin "1") (pinfunction "1_1") (pintype "passive"))
      (node (ref "SW2") (pin "COM") (pinfunction "COM_COM") (pintype "bidirectional"))
      (node (ref "U3") (pin "1") (pinfunction "S_1") (pintype "bidirectional"))
      (node (ref "U3") (pin "2") (pinfunction "S_2") (pintype "bidirectional"))
      (node (ref "U3") (pin "3") (pinfunction "S_3") (pintype "bidirectional"))
    )
    (net (code "77") (name "Net-(R13-Pad1)") (class "Default")
      (node (ref "R13") (pin "1") (pinfunction "1_1") (pintype "passive"))
      (node (ref "USB_HUB") (pin "A") (pinfunction "A_A") (pintype "passive"))
    )
    (net (code "78") (name "Net-(R17-Pad2)") (class "Default")
      (node (ref "R17") (pin "2") (pinfunction "2_2") (pintype "passive"))
      (node (ref "SW2") (pin "P1") (pinfunction "P1_P1") (pintype "bidirectional"))
    )
    (net (code "79") (name "Net-(U1-PWRBTN#)") (class "Default")
      (node (ref "R1") (pin "1") (pinfunction "1_1") (pintype "passive"))
      (node (ref "U1") (pin "17") (pinfunction "PWRBTN#_17") (pintype "bidirectional"))
    )
    (net (code "80") (name "Net-(U2-D-Pad5)") (class "Default")
      (node (ref "U2") (pin "5") (pinfunction "D_5") (pintype "bidirectional"))
      (node (ref "U2") (pin "6") (pinfunction "D_6") (pintype "bidirectional"))
      (node (ref "U2") (pin "7") (pinfunction "D_7") (pintype "bidirectional"))
      (node (ref "U2") (pin "8") (pinfunction "D_8") (pintype "bidirectional"))
      (node (ref "U3") (pin "5") (pinfunction "D_5") (pintype "bidirectional"))
      (node (ref "U3") (pin "6") (pinfunction "D_6") (pintype "bidirectional"))
      (node (ref "U3") (pin "7") (pinfunction "D_7") (pintype "bidirectional"))
      (node (ref "U3") (pin "8") (pinfunction "D_8") (pintype "bidirectional"))
    )
    (net (code "81") (name "Net-(U4A-D)") (class "Default")
      (node (ref "BOOT") (pin "C") (pinfunction "C_C") (pintype "passive"))
      (node (ref "U4") (pin "D1") (pinfunction "D_D1") (pintype "bidirectional"))
    )
    (net (code "82") (name "Net-(U5-B1)") (class "Default")
      (node (ref "U5") (pin "5") (pinfunction "B1_5") (pintype "bidirectional"))
      (node (ref "U6") (pin "3") (pinfunction "DIN_3") (pintype "bidirectional"))
    )
    (net (code "83") (name "Net-(U5-B2)") (class "Default")
      (node (ref "U5") (pin "4") (pinfunction "B2_4") (pintype "bidirectional"))
      (node (ref "U6") (pin "2") (pinfunction "DOUT_2") (pintype "bidirectional"))
    )
    (net (code "84") (name "Net-(U5-DIR1)") (class "Default")
      (node (ref "R27") (pin "1") (pinfunction "1_1") (pintype "passive"))
      (node (ref "U5") (pin "10") (pinfunction "DIR1_10") (pintype "bidirectional"))
    )
    (net (code "85") (name "Net-(U7-HYSTN)") (class "Default")
      (node (ref "R26") (pin "1") (pinfunction "1_1") (pintype "passive"))
      (node (ref "U7") (pin "2") (pinfunction "IN-_2") (pintype "bidirectional"))
      (node (ref "U7") (pin "5") (pinfunction "HYSTN_5") (pintype "bidirectional"))
      (node (ref "U7") (pin "7") (pinfunction "REF_7") (pintype "bidirectional"))
    )
    (net (code "86") (name "Net-(U7-HYSTP)") (class "Default")
      (node (ref "R23") (pin "1") (pinfunction "1_1") (pintype "passive"))
      (node (ref "R26") (pin "2") (pinfunction "2_2") (pintype "passive"))
      (node (ref "U7") (pin "6") (pinfunction "HYSTP_6") (pintype "bidirectional"))
    )
    (net (code "87") (name "Net-(U7-IN+)") (class "Default")
      (node (ref "R24") (pin "1") (pinfunction "1_1") (pintype "passive"))
      (node (ref "R25") (pin "2") (pinfunction "2_2") (pintype "passive"))
      (node (ref "U7") (pin "1") (pinfunction "IN+_1") (pintype "bidirectional"))
    )
    (net (code "88") (name "Net-(U7-OUT)") (class "Default")
      (node (ref "BATLOW") (pin "C") (pinfunction "C_C") (pintype "passive"))
      (node (ref "U7") (pin "4") (pinfunction "OUT_4") (pintype "bidirectional"))
    )
    (net (code "89") (name "VCC") (class "Default")
      (node (ref "BAT") (pin "P$3") (pinfunction "1_P$3") (pintype "passive"))
      (node (ref "C11") (pin "1") (pinfunction "1_1") (pintype "passive"))
      (node (ref "C16") (pin "2") (pinfunction "2_2") (pintype "passive"))
      (node (ref "C19") (pin "1") (pinfunction "1_1") (pintype "passive"))
      (node (ref "C24") (pin "1") (pinfunction "1_1") (pintype "passive"))
      (node (ref "C6") (pin "1") (pinfunction "1_1") (pintype "passive"))
      (node (ref "IC8") (pin "P10") (pinfunction "AVIN_P10") (pintype "bidirectional"))
      (node (ref "IC8") (pin "P11") (pinfunction "PVIN2_P11") (pintype "bidirectional"))
      (node (ref "IC8") (pin "P12") (pinfunction "PVIN1_P12") (pintype "bidirectional"))
      (node (ref "IC8") (pin "P13") (pinfunction "EN_P13") (pintype "bidirectional"))
      (node (ref "IC9") (pin "P10") (pinfunction "AVIN_P10") (pintype "bidirectional"))
      (node (ref "IC9") (pin "P11") (pinfunction "PVIN2_P11") (pintype "bidirectional"))
      (node (ref "IC9") (pin "P12") (pinfunction "PVIN1_P12") (pintype "bidirectional"))
      (node (ref "IC9") (pin "P13") (pinfunction "EN_P13") (pintype "bidirectional"))
      (node (ref "J10") (pin "PWR") (pinfunction "PWR_PWR") (pintype "bidirectional"))
      (node (ref "J11") (pin "PWR") (pinfunction "PWR_PWR") (pintype "bidirectional"))
      (node (ref "J12") (pin "PWR") (pinfunction "PWR_PWR") (pintype "bidirectional"))
      (node (ref "J13") (pin "PWR") (pinfunction "PWR_PWR") (pintype "bidirectional"))
      (node (ref "J14") (pin "PWR") (pinfunction "PWR_PWR") (pintype "bidirectional"))
      (node (ref "J15") (pin "PWR") (pinfunction "PWR_PWR") (pintype "bidirectional"))
      (node (ref "JP3") (pin "2") (pinfunction "2_2") (pintype "passive"))
      (node (ref "R22") (pin "2") (pinfunction "2_2") (pintype "passive"))
      (node (ref "R24") (pin "2") (pinfunction "2_2") (pintype "passive"))
      (node (ref "R7") (pin "1") (pinfunction "1_1") (pintype "passive"))
      (node (ref "R8") (pin "1") (pinfunction "1_1") (pintype "passive"))
      (node (ref "U7") (pin "8") (pinfunction "VCC_8") (pintype "bidirectional"))
    )
    (net (code "90") (name "unconnected-(IC2-CBUS0-Pad12)") (class "Default")
      (node (ref "IC2") (pin "12") (pinfunction "CBUS0_12") (pintype "bidirectional"))
    )
    (net (code "91") (name "unconnected-(IC2-CBUS1-Pad11)") (class "Default")
      (node (ref "IC2") (pin "11") (pinfunction "CBUS1_11") (pintype "bidirectional"))
    )
    (net (code "92") (name "unconnected-(IC2-CBUS2-Pad5)") (class "Default")
      (node (ref "IC2") (pin "5") (pinfunction "CBUS2_5") (pintype "bidirectional"))
    )
    (net (code "93") (name "unconnected-(IC2-CBUS3-Pad14)") (class "Default")
      (node (ref "IC2") (pin "14") (pinfunction "CBUS3_14") (pintype "bidirectional"))
    )
    (net (code "94") (name "unconnected-(IC2-~{CTS}-Pad4)") (class "Default")
      (node (ref "IC2") (pin "4") (pinfunction "~{CTS}_4") (pintype "input"))
    )
    (net (code "95") (name "unconnected-(IC2-~{RTS}-Pad16)") (class "Default")
      (node (ref "IC2") (pin "16") (pinfunction "~{RTS}_16") (pintype "output"))
    )
    (net (code "96") (name "unconnected-(IC3-CBUS3-Pad14)") (class "Default")
      (node (ref "IC3") (pin "14") (pinfunction "CBUS3_14") (pintype "bidirectional"))
    )
    (net (code "97") (name "unconnected-(IC3-~{CTS}-Pad4)") (class "Default")
      (node (ref "IC3") (pin "4") (pinfunction "~{CTS}_4") (pintype "input"))
    )
    (net (code "98") (name "unconnected-(IC3-~{RTS}-Pad16)") (class "Default")
      (node (ref "IC3") (pin "16") (pinfunction "~{RTS}_16") (pintype "output"))
    )
    (net (code "99") (name "unconnected-(IC5-HS_IND-Pad25)") (class "Default")
      (node (ref "IC5") (pin "25") (pinfunction "HS_IND_25") (pintype "bidirectional"))
    )
    (net (code "100") (name "unconnected-(IC5-SCL-Pad24)") (class "Default")
      (node (ref "IC5") (pin "24") (pinfunction "SCL_24") (pintype "bidirectional"))
    )
    (net (code "101") (name "unconnected-(IC5-SDA-Pad22)") (class "Default")
      (node (ref "IC5") (pin "22") (pinfunction "SDA_22") (pintype "bidirectional"))
    )
    (net (code "102") (name "unconnected-(U1-FAULT-Pad19)") (class "Default")
      (node (ref "U1") (pin "19") (pinfunction "FAULT_19") (pintype "bidirectional"))
    )
    (net (code "103") (name "unconnected-(U1-FW_RCVR-Pad69)") (class "Default")
      (node (ref "U1") (pin "69") (pinfunction "FW_RCVR_69") (pintype "bidirectional"))
    )
    (net (code "104") (name "unconnected-(U1-GP12_PWM0-Pad35)") (class "Default")
      (node (ref "U1") (pin "35") (pinfunction "GP12_PWM0_35") (pintype "bidirectional"))
    )
    (net (code "105") (name "unconnected-(U1-GP13_PWM1-Pad33)") (class "Default")
      (node (ref "U1") (pin "33") (pinfunction "GP13_PWM1_33") (pintype "bidirectional"))
    )
    (net (code "106") (name "unconnected-(U1-GP15-Pad42)") (class "Default")
      (node (ref "U1") (pin "42") (pinfunction "GP15_42") (pintype "bidirectional"))
    )
    (net (code "107") (name "unconnected-(U1-GP19_I2C_1_SCL-Pad41)") (class "Default")
      (node (ref "U1") (pin "41") (pinfunction "GP19_I2C_1_SCL_41") (pintype "bidirectional"))
    )
    (net (code "108") (name "unconnected-(U1-GP20_I2C_1_SDA-Pad43)") (class "Default")
      (node (ref "U1") (pin "43") (pinfunction "GP20_I2C_1_SDA_43") (pintype "bidirectional"))
    )
    (net (code "109") (name "unconnected-(U1-GP27_I2C_6_SCL-Pad45)") (class "Default")
      (node (ref "U1") (pin "45") (pinfunction "GP27_I2C_6_SCL_45") (pintype "bidirectional"))
    )
    (net (code "110") (name "unconnected-(U1-GP28_I2C_6_SDA-Pad47)") (class "Default")
      (node (ref "U1") (pin "47") (pinfunction "GP28_I2C_6_SDA_47") (pintype "bidirectional"))
    )
    (net (code "111") (name "unconnected-(U1-GP40_I2S_2_CLK-Pad52)") (class "Default")
      (node (ref "U1") (pin "52") (pinfunction "GP40_I2S_2_CLK_52") (pintype "bidirectional"))
    )
    (net (code "112") (name "unconnected-(U1-GP41_I2S_2_FS-Pad54)") (class "Default")
      (node (ref "U1") (pin "54") (pinfunction "GP41_I2S_2_FS_54") (pintype "bidirectional"))
    )
    (net (code "113") (name "unconnected-(U1-GP42_I2S_2_RXD-Pad50)") (class "Default")
      (node (ref "U1") (pin "50") (pinfunction "GP42_I2S_2_RXD_50") (pintype "bidirectional"))
    )
    (net (code "114") (name "unconnected-(U1-GP43_I2S_2_TXD-Pad56)") (class "Default")
      (node (ref "U1") (pin "56") (pinfunction "GP43_I2S_2_TXD_56") (pintype "bidirectional"))
    )
    (net (code "115") (name "unconnected-(U1-GP77_SD_0_CD#-Pad60)") (class "Default")
      (node (ref "U1") (pin "60") (pinfunction "GP77_SD_0_CD#_60") (pintype "bidirectional"))
    )
    (net (code "116") (name "unconnected-(U1-GP78_SD_0_CLK-Pad58)") (class "Default")
      (node (ref "U1") (pin "58") (pinfunction "GP78_SD_0_CLK_58") (pintype "bidirectional"))
    )
    (net (code "117") (name "unconnected-(U1-GP79_SD_0_CMD-Pad62)") (class "Default")
      (node (ref "U1") (pin "62") (pinfunction "GP79_SD_0_CMD_62") (pintype "bidirectional"))
    )
    (net (code "118") (name "unconnected-(U1-GP80_SD_0_DAT0-Pad66)") (class "Default")
      (node (ref "U1") (pin "66") (pinfunction "GP80_SD_0_DAT0_66") (pintype "bidirectional"))
    )
    (net (code "119") (name "unconnected-(U1-GP81_SD_0_DAT1-Pad70)") (class "Default")
      (node (ref "U1") (pin "70") (pinfunction "GP81_SD_0_DAT1_70") (pintype "bidirectional"))
    )
    (net (code "120") (name "unconnected-(U1-GP82_SD_0_DAT2-Pad64)") (class "Default")
      (node (ref "U1") (pin "64") (pinfunction "GP82_SD_0_DAT2_64") (pintype "bidirectional"))
    )
    (net (code "121") (name "unconnected-(U1-GP83_SD_0_DAT3-Pad68)") (class "Default")
      (node (ref "U1") (pin "68") (pinfunction "GP83_SD_0_DAT3_68") (pintype "bidirectional"))
    )
    (net (code "122") (name "unconnected-(U1-GP84_SD_CLK_FB-Pad44)") (class "Default")
      (node (ref "U1") (pin "44") (pinfunction "GP84_SD_CLK_FB_44") (pintype "bidirectional"))
    )
    (net (code "123") (name "unconnected-(U1-GP109_SPI_2_CLK-Pad55)") (class "Default")
      (node (ref "U1") (pin "55") (pinfunction "GP109_SPI_2_CLK_55") (pintype "bidirectional"))
    )
    (net (code "124") (name "unconnected-(U1-GP110_SPI_2_FS0-Pad53)") (class "Default")
      (node (ref "U1") (pin "53") (pinfunction "GP110_SPI_2_FS0_53") (pintype "bidirectional"))
    )
    (net (code "125") (name "unconnected-(U1-GP111_SPI_2_FS1-Pad51)") (class "Default")
      (node (ref "U1") (pin "51") (pinfunction "GP111_SPI_2_FS1_51") (pintype "bidirectional"))
    )
    (net (code "126") (name "unconnected-(U1-GP114_SPI_2_RXD-Pad59)") (class "Default")
      (node (ref "U1") (pin "59") (pinfunction "GP114_SPI_2_RXD_59") (pintype "bidirectional"))
    )
    (net (code "127") (name "unconnected-(U1-GP115_SPI_2_TXD-Pad57)") (class "Default")
      (node (ref "U1") (pin "57") (pinfunction "GP115_SPI_2_TXD_57") (pintype "bidirectional"))
    )
    (net (code "128") (name "unconnected-(U1-GP128_UART_1_CTS-Pad65)") (class "Default")
      (node (ref "U1") (pin "65") (pinfunction "GP128_UART_1_CTS_65") (pintype "bidirectional"))
    )
    (net (code "129") (name "unconnected-(U1-GP129_UART_1_RTS-Pad63)") (class "Default")
      (node (ref "U1") (pin "63") (pinfunction "GP129_UART_1_RTS_63") (pintype "bidirectional"))
    )
    (net (code "130") (name "unconnected-(U1-GP165-Pad25)") (class "Default")
      (node (ref "U1") (pin "25") (pinfunction "GP165_25") (pintype "bidirectional"))
    )
    (net (code "131") (name "unconnected-(U1-GP182_PWM2-Pad37)") (class "Default")
      (node (ref "U1") (pin "37") (pinfunction "GP182_PWM2_37") (pintype "bidirectional"))
    )
    (net (code "132") (name "unconnected-(U1-GP183_PWM3-Pad39)") (class "Default")
      (node (ref "U1") (pin "39") (pinfunction "GP183_PWM3_39") (pintype "bidirectional"))
    )
    (net (code "133") (name "unconnected-(U1-MSIC_SLP_CLK-Pad7)") (class "Default")
      (node (ref "U1") (pin "7") (pinfunction "MSIC_SLP_CLK_7") (pintype "bidirectional"))
    )
    (net (code "134") (name "unconnected-(U1-OSC_CLK_OUT_0-Pad67)") (class "Default")
      (node (ref "U1") (pin "67") (pinfunction "OSC_CLK_OUT_0_67") (pintype "bidirectional"))
    )
    (net (code "135") (name "unconnected-(U1-PSW-Pad21)") (class "Default")
      (node (ref "U1") (pin "21") (pinfunction "PSW_21") (pintype "bidirectional"))
    )
    (net (code "136") (name "unconnected-(U1-RCVR_MODE-Pad31)") (class "Default")
      (node (ref "U1") (pin "31") (pinfunction "RCVR_MODE_31") (pintype "bidirectional"))
    )
    (net (code "137") (name "unconnected-(U1-USB_VBUS-Pad20)") (class "Default")
      (node (ref "U1") (pin "20") (pinfunction "USB_VBUS_20") (pintype "bidirectional"))
    )
    (net (code "138") (name "unconnected-(U1-V_VAT_BKUP-Pad23)") (class "Default")
      (node (ref "U1") (pin "23") (pinfunction "V_VAT_BKUP_23") (pintype "bidirectional"))
    )
    (net (code "139") (name "unconnected-(U6-AD0-Pad20)") (class "Default")
      (node (ref "U6") (pin "20") (pinfunction "AD0_20") (pintype "bidirectional"))
    )
    (net (code "140") (name "unconnected-(U6-AD1-Pad19)") (class "Default")
      (node (ref "U6") (pin "19") (pinfunction "AD1_19") (pintype "bidirectional"))
    )
    (net (code "141") (name "unconnected-(U6-AD2-Pad18)") (class "Default")
      (node (ref "U6") (pin "18") (pinfunction "AD2_18") (pintype "bidirectional"))
    )
    (net (code "142") (name "unconnected-(U6-AD3-Pad17)") (class "Default")
      (node (ref "U6") (pin "17") (pinfunction "AD3_17") (pintype "bidirectional"))
    )
    (net (code "143") (name "unconnected-(U6-DIO4-Pad11)") (class "Default")
      (node (ref "U6") (pin "11") (pinfunction "DIO4_11") (pintype "bidirectional"))
    )
    (net (code "144") (name "unconnected-(U6-DIO5-Pad15)") (class "Default")
      (node (ref "U6") (pin "15") (pinfunction "DIO5_15") (pintype "bidirectional"))
    )
    (net (code "145") (name "unconnected-(U6-DIO12-Pad4)") (class "Default")
      (node (ref "U6") (pin "4") (pinfunction "DIO12_4") (pintype "bidirectional"))
    )
    (net (code "146") (name "unconnected-(U6-ON-Pad13)") (class "Default")
      (node (ref "U6") (pin "13") (pinfunction "ON_13") (pintype "bidirectional"))
    )
    (net (code "147") (name "unconnected-(U6-PWM-Pad7)") (class "Default")
      (node (ref "U6") (pin "7") (pinfunction "PWM_7") (pintype "bidirectional"))
    )
    (net (code "148") (name "unconnected-(U6-PWM0-Pad6)") (class "Default")
      (node (ref "U6") (pin "6") (pinfunction "PWM0_6") (pintype "bidirectional"))
    )
    (net (code "149") (name "unconnected-(U6-RESERVED-Pad8)") (class "Default")
      (node (ref "U6") (pin "8") (pinfunction "RESERVED_8") (pintype "bidirectional"))
    )
    (net (code "150") (name "unconnected-(U6-VREF-Pad14)") (class "Default")
      (node (ref "U6") (pin "14") (pinfunction "VREF_14") (pintype "bidirectional"))
    )
    (net (code "151") (name "unconnected-(U6-~{CTS}-Pad12)") (class "Default")
      (node (ref "U6") (pin "12") (pinfunction "~{CTS}_12") (pintype "bidirectional"))
    )
    (net (code "152") (name "unconnected-(U6-~{DTR}-Pad9)") (class "Default")
      (node (ref "U6") (pin "9") (pinfunction "~{DTR}_9") (pintype "bidirectional"))
    )
    (net (code "153") (name "unconnected-(U6-~{RESET}-Pad5)") (class "Default")
      (node (ref "U6") (pin "5") (pinfunction "~{RESET}_5") (pintype "bidirectional"))
    )
    (net (code "154") (name "unconnected-(U6-~{RTS}-Pad16)") (class "Default")
      (node (ref "U6") (pin "16") (pinfunction "~{RTS}_16") (pintype "bidirectional"))
    )
  )
)
